# LCD.net
KiCad netlist of a schematic drawn in Altium Designer
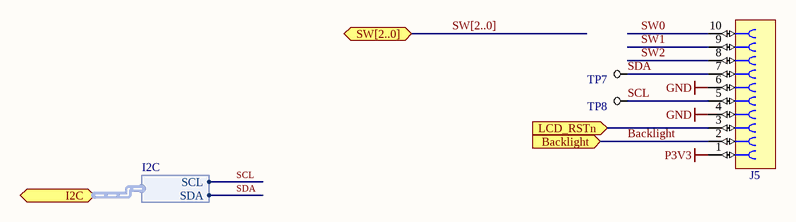
[diagram p0: LCD.SchDoc]

(export (version "E")
  (design (tool "Eeschema 10.0.6"))
  (components
    (comp (ref "J5")
      (value "FFC")
      (footprint "WURTH_686 110 144 22")
      (description "Connector 10 Female")
      (fields
        (field (name "PART NUMBER") "WURTH_686 110 144 22")
        (field (name "MANUFACTURER") "WURTH ELEKTRONIK")
        (field (name "AUTHOR") "CERN DEM JMW")
      )
      (libsource (lib "Connectors") (part "Connector 10 Female"))
    )
    (comp (ref "TP7")
      (value "TP")
      (footprint "TP")
      (description "Testpoint")
      (libsource (lib "LIBRARY_SCH") (part "TP"))
    )
    (comp (ref "TP8")
      (value "TP")
      (footprint "TP")
      (description "Testpoint")
      (libsource (lib "LIBRARY_SCH") (part "TP"))
    )
  )
  (nets
    (net (code "2") (name "/Backlight") (class "Default")
      (node (ref "J5") (pin "2") (pinfunction "2_2") (pintype "bidirectional"))
    )
    (net (code "3") (name "/LCD_RSTn") (class "Default")
      (node (ref "J5") (pin "3") (pinfunction "3_3") (pintype "bidirectional"))
    )
    (net (code "4") (name "/SCL") (class "Default")
      (node (ref "J5") (pin "5") (pinfunction "5_5") (pintype "bidirectional"))
      (node (ref "TP8") (pin "1") (pintype "passive"))
    )
    (net (code "5") (name "/SDA") (class "Default")
      (node (ref "J5") (pin "7") (pinfunction "7_7") (pintype "bidirectional"))
      (node (ref "TP7") (pin "1") (pintype "passive"))
    )
    (net (code "6") (name "/SW0") (class "Default")
      (node (ref "J5") (pin "10") (pinfunction "10_10") (pintype "bidirectional"))
    )
    (net (code "7") (name "/SW1") (class "Default")
      (node (ref "J5") (pin "9") (pinfunction "9_9") (pintype "bidirectional"))
    )
    (net (code "8") (name "/SW2") (class "Default")
      (node (ref "J5") (pin "8") (pinfunction "8_8") (pintype "bidirectional"))
    )
    (net (code "11") (name "GND") (class "Default")
      (node (ref "J5") (pin "4") (pinfunction "4_4") (pintype "bidirectional"))
      (node (ref "J5") (pin "6") (pinfunction "6_6") (pintype "bidirectional"))
    )
    (net (code "12") (name "P3V3") (class "Default")
      (node (ref "J5") (pin "1") (pinfunction "1_1") (pintype "bidirectional"))
    )
  )
)
